# Deneigus_Controle_Deplacement.net
KiCad netlist of a schematic drawn in Altium Designer
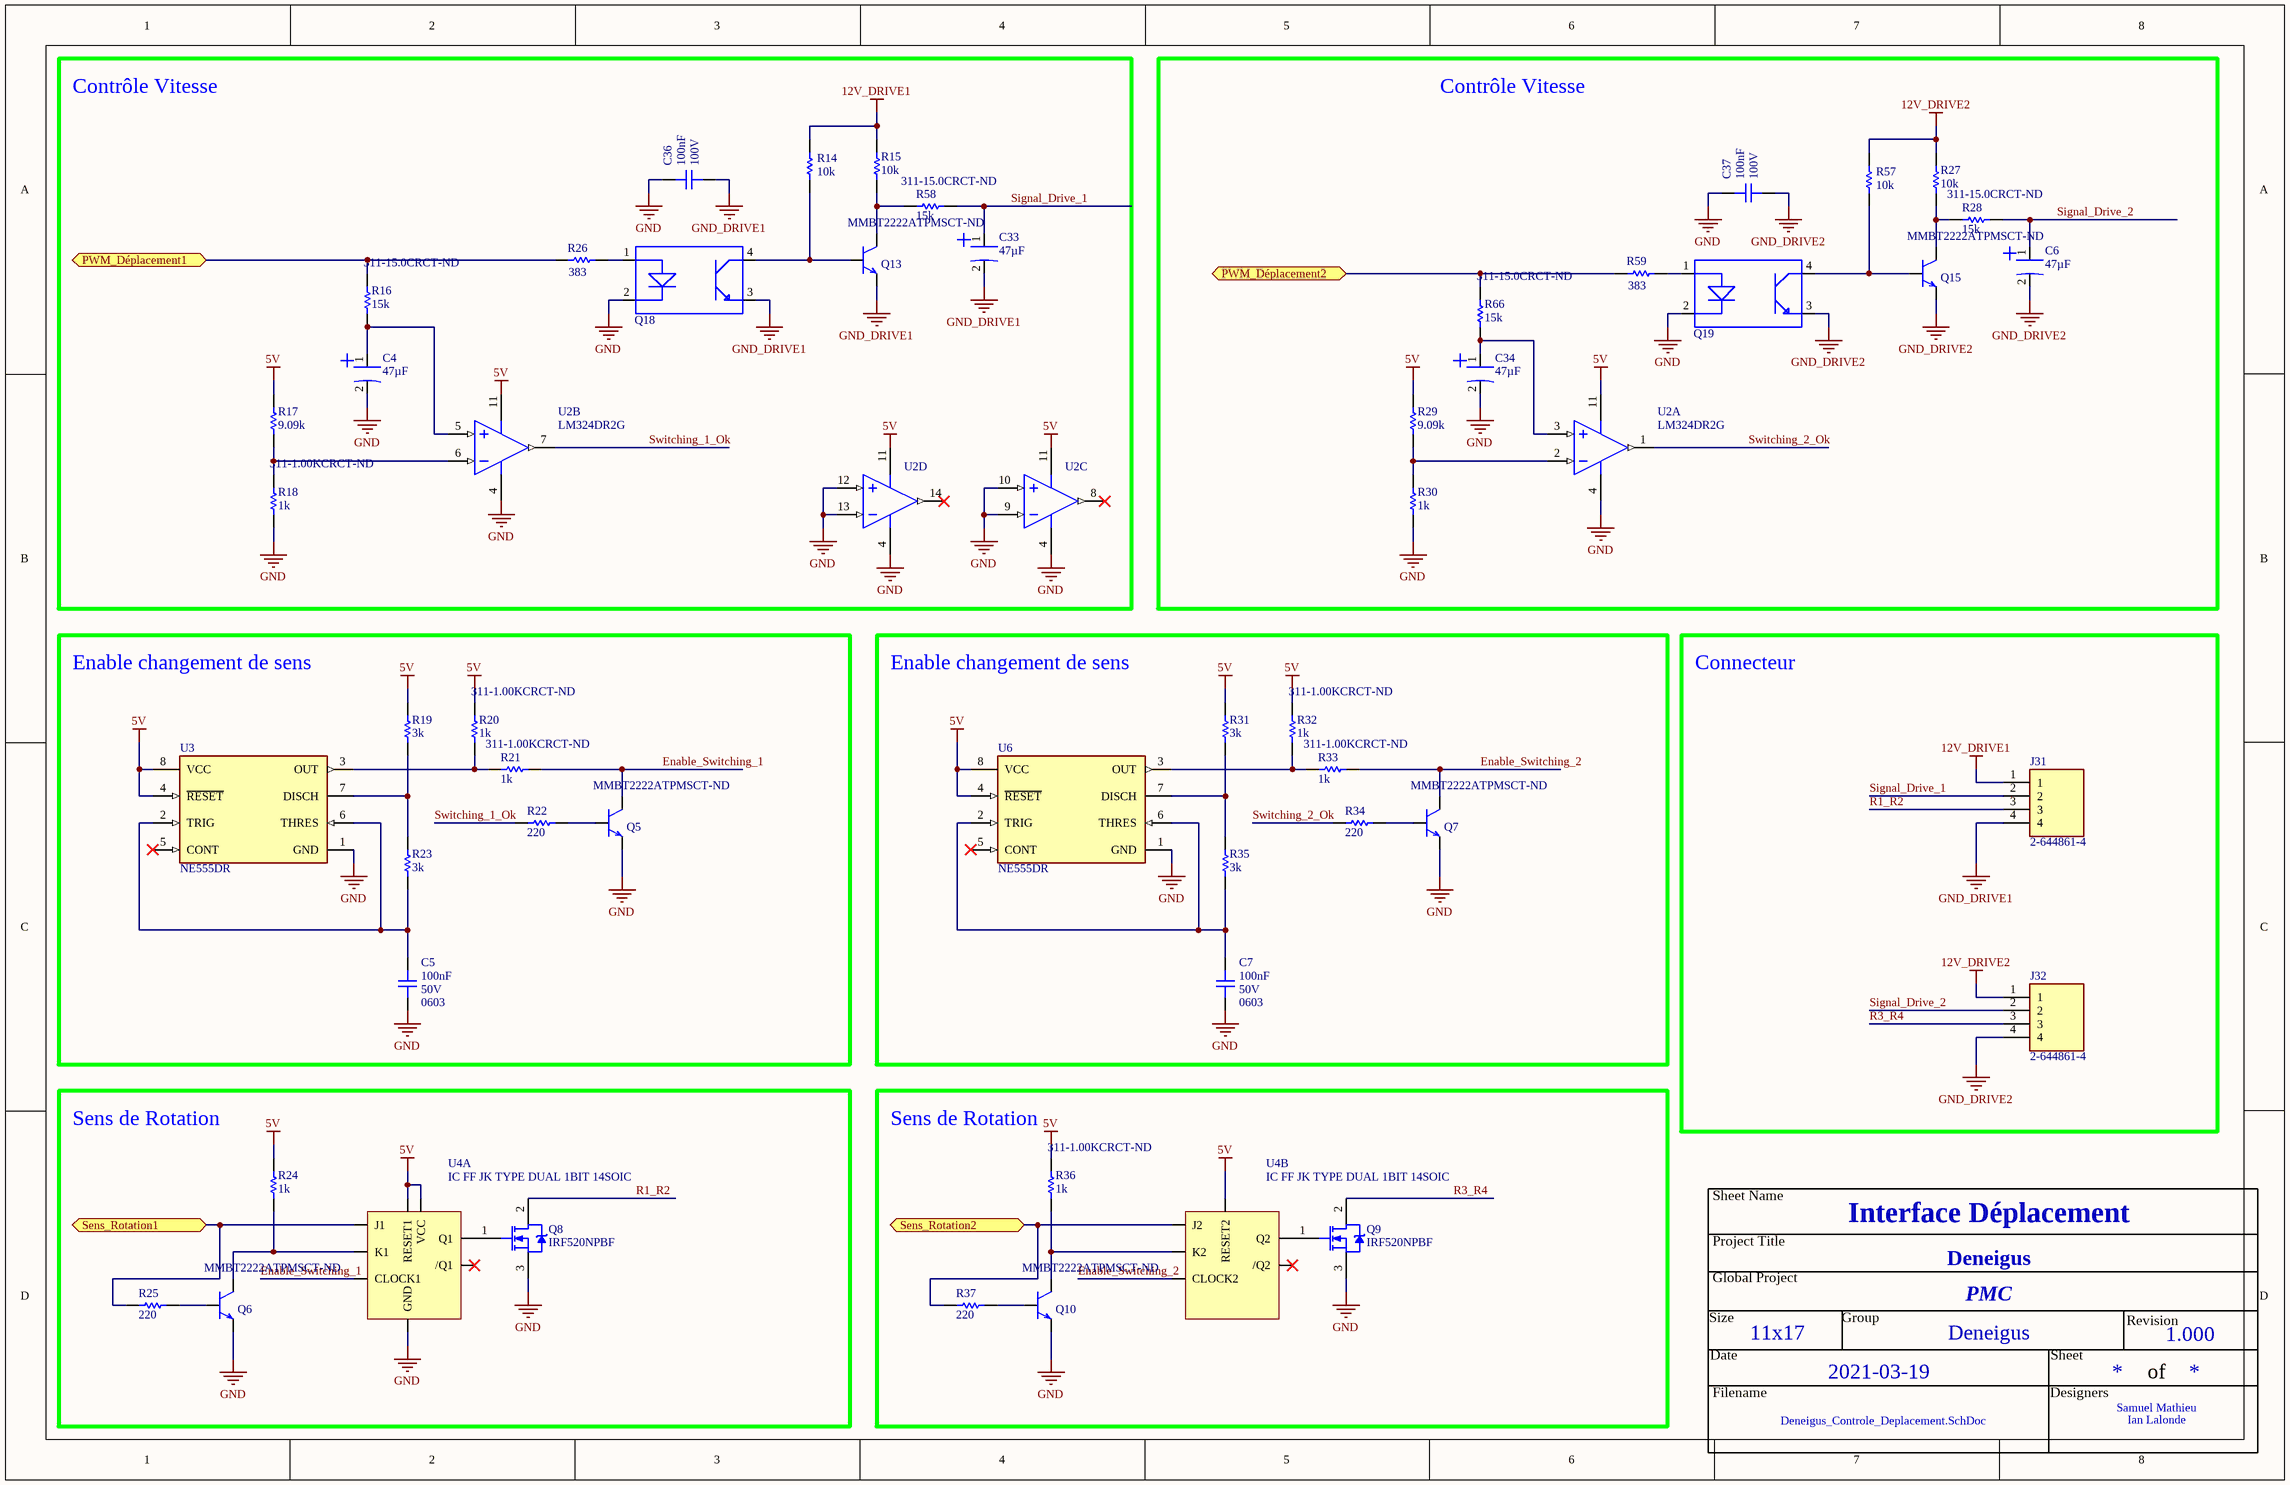
[diagram p0: Deneigus_Controle_Deplacement.SchDoc]

(export (version "E")
  (design (tool "Eeschema 10.0.6"))
  (components
    (comp (ref "C4")
      (value "47µF")
      (footprint "47uF")
      (fields
        (field (name "MFG") "Würth Elektronik")
        (field (name "MFG PART NUMBER") "875105344006")
        (field (name "Comment") "CAP ALUM POLY 47UF 20% 16V SMD")
      )
      (libsource (lib "S7CAS-APP1") (part "47µF SMD"))
    )
    (comp (ref "C5")
      (value "100nF")
      (footprint "CAP_0603")
      (description "CAP - 0603")
      (fields
        (field (name "VOLTAGE") "50V")
        (field (name "PACKAGE") "0603")
        (field (name "CREATEDBY") "Jonathan Bouchard")
      )
      (libsource (lib "S7CAS_LIB2021") (part "CAP - 0603"))
    )
    (comp (ref "C6")
      (value "47µF")
      (footprint "47uF")
      (fields
        (field (name "MFG") "Würth Elektronik")
        (field (name "MFG PART NUMBER") "875105344006")
        (field (name "Comment") "CAP ALUM POLY 47UF 20% 16V SMD")
      )
      (libsource (lib "S7CAS-APP1") (part "47µF SMD"))
    )
    (comp (ref "C7")
      (value "100nF")
      (footprint "CAP_0603")
      (description "CAP - 0603")
      (fields
        (field (name "VOLTAGE") "50V")
        (field (name "PACKAGE") "0603")
        (field (name "CREATEDBY") "Jonathan Bouchard")
      )
      (libsource (lib "S7CAS_LIB2021") (part "CAP - 0603"))
    )
    (comp (ref "C33")
      (value "47µF")
      (footprint "47uF")
      (fields
        (field (name "MFG") "Würth Elektronik")
        (field (name "MFG PART NUMBER") "875105344006")
        (field (name "Comment") "CAP ALUM POLY 47UF 20% 16V SMD")
      )
      (libsource (lib "S7CAS-APP1") (part "47µF SMD"))
    )
    (comp (ref "C34")
      (value "47µF")
      (footprint "47uF")
      (fields
        (field (name "MFG") "Würth Elektronik")
        (field (name "MFG PART NUMBER") "875105344006")
        (field (name "Comment") "CAP ALUM POLY 47UF 20% 16V SMD")
      )
      (libsource (lib "S7CAS-APP1") (part "47µF SMD"))
    )
    (comp (ref "C36")
      (value "100nF")
      (footprint "CAP_0805")
      (description "CAP - 0805")
      (fields
        (field (name "MFG") "Murata Electronics")
        (field (name "MFG PART NUMBER") "GRM21BR61H106ME43L")
        (field (name "VOLTAGE") "100V")
        (field (name "CREATEDBY") "Jonathan Bouchard")
      )
      (libsource (lib "S7CAS_LIB2021(1)") (part "CAP - 0805"))
    )
    (comp (ref "C37")
      (value "100nF")
      (footprint "CAP_0805")
      (description "CAP - 0805")
      (fields
        (field (name "MFG") "Murata Electronics")
        (field (name "MFG PART NUMBER") "GRM21BR61H106ME43L")
        (field (name "VOLTAGE") "100V")
        (field (name "CREATEDBY") "Jonathan Bouchard")
      )
      (libsource (lib "S7CAS_LIB2021(1)") (part "CAP - 0805"))
    )
    (comp (ref "J31")
      (value "2-644861-4")
      (footprint "TE_2-644861-4:TE_2-644861-4")
      (description "Connector Header Through Hole 4 position 0.100 (2.54mm)")
      (fields (field (name "MF") "TE Connectivity"))
      (libsource (lib "2-644861-4") (part "2-644861-4"))
    )
    (comp (ref "J32")
      (value "2-644861-4")
      (footprint "TE_2-644861-4:TE_2-644861-4")
      (description "Connector Header Through Hole 4 position 0.100 (2.54mm)")
      (fields (field (name "MF") "TE Connectivity"))
      (libsource (lib "2-644861-4") (part "2-644861-4"))
    )
    (comp (ref "Q5")
      (value "TRANS NPN 40V 0.2A SOT23")
      (footprint "SOT-23")
      (description "Transistor: 200mA 200mW NPN General-Purpose Amplifier, SOT-23, 7IN. Reel")
      (fields
        (field (name "MANUFACTURER") "MCC")
        (field (name "MANUFACTURER PART NUMBER") "MMBT3904-TP")
        (field (name "SUPPLIER PART NUMBER 1") "MMBT2222ATPMSCT-ND")
      )
      (libsource (lib "S7CAS-APP1") (part "NPN 3904 SMD"))
    )
    (comp (ref "Q6")
      (value "TRANS NPN 40V 0.2A SOT23")
      (footprint "SOT-23")
      (description "Transistor: 200mA 200mW NPN General-Purpose Amplifier, SOT-23, 7IN. Reel")
      (fields
        (field (name "MANUFACTURER") "MCC")
        (field (name "MANUFACTURER PART NUMBER") "MMBT3904-TP")
        (field (name "SUPPLIER PART NUMBER 1") "MMBT2222ATPMSCT-ND")
      )
      (libsource (lib "S7CAS-APP1") (part "NPN 3904 SMD"))
    )
    (comp (ref "Q7")
      (value "TRANS NPN 40V 0.2A SOT23")
      (footprint "SOT-23")
      (description "Transistor: 200mA 200mW NPN General-Purpose Amplifier, SOT-23, 7IN. Reel")
      (fields
        (field (name "MANUFACTURER") "MCC")
        (field (name "MANUFACTURER PART NUMBER") "MMBT3904-TP")
        (field (name "SUPPLIER PART NUMBER 1") "MMBT2222ATPMSCT-ND")
      )
      (libsource (lib "S7CAS-APP1") (part "NPN 3904 SMD"))
    )
    (comp (ref "Q8")
      (value "IRF520NPBF")
      (footprint "INTR-TO-220AB-3")
      (description "HEXFET(R) Power MOSFET, 100 V, 9.7 A, 0.2 Ohm, -55 to 175 degC, 3-Pin FM (TO-220AB), RoHS, Tube")
      (fields (field (name "POWER") "48W") (field (name "MANUFACTURER") "International Rectifier"))
      (libsource (lib "Université de Sherbrooke") (part "NEMOS-GDS-3_B"))
    )
    (comp (ref "Q9")
      (value "IRF520NPBF")
      (footprint "INTR-TO-220AB-3")
      (description "HEXFET(R) Power MOSFET, 100 V, 9.7 A, 0.2 Ohm, -55 to 175 degC, 3-Pin FM (TO-220AB), RoHS, Tube")
      (fields (field (name "POWER") "48W") (field (name "MANUFACTURER") "International Rectifier"))
      (libsource (lib "Université de Sherbrooke") (part "NEMOS-GDS-3_B"))
    )
    (comp (ref "Q10")
      (value "TRANS NPN 40V 0.2A SOT23")
      (footprint "SOT-23")
      (description "Transistor: 200mA 200mW NPN General-Purpose Amplifier, SOT-23, 7IN. Reel")
      (fields
        (field (name "MANUFACTURER") "MCC")
        (field (name "MANUFACTURER PART NUMBER") "MMBT3904-TP")
        (field (name "SUPPLIER PART NUMBER 1") "MMBT2222ATPMSCT-ND")
      )
      (libsource (lib "S7CAS-APP1") (part "NPN 3904 SMD"))
    )
    (comp (ref "Q13")
      (value "TRANS NPN 40V 0.2A SOT23")
      (footprint "SOT-23")
      (description "Transistor: 200mA 200mW NPN General-Purpose Amplifier, SOT-23, 7IN. Reel")
      (fields
        (field (name "MANUFACTURER") "MCC")
        (field (name "MANUFACTURER PART NUMBER") "MMBT3904-TP")
        (field (name "SUPPLIER PART NUMBER 1") "MMBT2222ATPMSCT-ND")
      )
      (libsource (lib "S7CAS-APP1") (part "NPN 3904 SMD"))
    )
    (comp (ref "Q15")
      (value "TRANS NPN 40V 0.2A SOT23")
      (footprint "SOT-23")
      (description "Transistor: 200mA 200mW NPN General-Purpose Amplifier, SOT-23, 7IN. Reel")
      (fields
        (field (name "MANUFACTURER") "MCC")
        (field (name "MANUFACTURER PART NUMBER") "MMBT3904-TP")
        (field (name "SUPPLIER PART NUMBER 1") "MMBT2222ATPMSCT-ND")
      )
      (libsource (lib "S7CAS-APP1") (part "NPN 3904 SMD"))
    )
    (comp (ref "Q18")
      (value "WL-OCPT OPTOCOUPLER PHOTOTRANSIS")
      (footprint "WL-OCPT OPTOCOUPLER PHOTOTRANSIS")
      (description "Optoisolator Transistor Output 3750Vrms 1 Channel 4-SOP")
      (libsource (lib "S7CAS-APP1") (part "WL-OCPT OPTOCOUPLER PHOTOTRANSIS"))
    )
    (comp (ref "Q19")
      (value "WL-OCPT OPTOCOUPLER PHOTOTRANSIS")
      (footprint "WL-OCPT OPTOCOUPLER PHOTOTRANSIS")
      (description "Optoisolator Transistor Output 3750Vrms 1 Channel 4-SOP")
      (libsource (lib "S7CAS-APP1") (part "WL-OCPT OPTOCOUPLER PHOTOTRANSIS"))
    )
    (comp (ref "R14")
      (value "10k")
      (footprint "RES_0805")
      (description "Resistor")
      (fields (field (name "Comment") "Res1") (field (name "PUBLISHER") "Altium Limited"))
      (libsource (lib "Miscellaneous Devices") (part "Res1"))
    )
    (comp (ref "R15")
      (value "10k")
      (footprint "RES_0805")
      (description "Resistor")
      (fields (field (name "Comment") "Res1") (field (name "PUBLISHER") "Altium Limited"))
      (libsource (lib "Miscellaneous Devices") (part "Res1"))
    )
    (comp (ref "R16")
      (value "15k")
      (footprint "RES_0805")
      (description "Resistor")
      (fields
        (field (name "SUPPLIER PART NUMBER 1") "311-15.0CRCT-ND")
        (field (name "Comment") "Res1")
        (field (name "PUBLISHER") "Altium Limited")
      )
      (libsource (lib "Miscellaneous Devices") (part "Res1"))
    )
    (comp (ref "R17")
      (value "9.09k")
      (footprint "RES_0805")
      (description "Resistor")
      (fields (field (name "Comment") "Res1") (field (name "PUBLISHER") "Altium Limited"))
      (libsource (lib "Miscellaneous Devices") (part "Res1"))
    )
    (comp (ref "R18")
      (value "1k")
      (footprint "RES_0805")
      (description "Resistor")
      (fields
        (field (name "SUPPLIER PART NUMBER 1") "311-1.00KCRCT-ND")
        (field (name "Comment") "Res1")
        (field (name "PUBLISHER") "Altium Limited")
      )
      (libsource (lib "Miscellaneous Devices") (part "Res1"))
    )
    (comp (ref "R19")
      (value "3k")
      (footprint "RES_0805")
      (description "Resistor")
      (fields (field (name "Comment") "Res1") (field (name "PUBLISHER") "Altium Limited"))
      (libsource (lib "Miscellaneous Devices") (part "Res1"))
    )
    (comp (ref "R20")
      (value "1k")
      (footprint "RES_0805")
      (description "Resistor")
      (fields
        (field (name "SUPPLIER PART NUMBER 1") "311-1.00KCRCT-ND")
        (field (name "Comment") "Res1")
        (field (name "PUBLISHER") "Altium Limited")
      )
      (libsource (lib "Miscellaneous Devices") (part "Res1"))
    )
    (comp (ref "R21")
      (value "1k")
      (footprint "RES_0805")
      (description "Resistor")
      (fields
        (field (name "SUPPLIER PART NUMBER 1") "311-1.00KCRCT-ND")
        (field (name "Comment") "Res1")
        (field (name "PUBLISHER") "Altium Limited")
      )
      (libsource (lib "Miscellaneous Devices") (part "Res1"))
    )
    (comp (ref "R22")
      (value "220")
      (footprint "RES_0805")
      (description "Resistor")
      (fields (field (name "Comment") "Res1") (field (name "PUBLISHER") "Altium Limited"))
      (libsource (lib "Miscellaneous Devices") (part "Res1"))
    )
    (comp (ref "R23")
      (value "3k")
      (footprint "RES_0805")
      (description "Resistor")
      (fields (field (name "Comment") "Res1") (field (name "PUBLISHER") "Altium Limited"))
      (libsource (lib "Miscellaneous Devices") (part "Res1"))
    )
    (comp (ref "R24")
      (value "1k")
      (footprint "RES_0805")
      (description "Resistor")
      (fields (field (name "Comment") "Res1") (field (name "PUBLISHER") "Altium Limited"))
      (libsource (lib "Miscellaneous Devices") (part "Res1"))
    )
    (comp (ref "R25")
      (value "220")
      (footprint "RES_0805")
      (description "Resistor")
      (fields (field (name "Comment") "Res1") (field (name "PUBLISHER") "Altium Limited"))
      (libsource (lib "Miscellaneous Devices") (part "Res1"))
    )
    (comp (ref "R26")
      (value "383")
      (footprint "RES_0805")
      (description "Resistor")
      (fields (field (name "Comment") "Res1") (field (name "PUBLISHER") "Altium Limited"))
      (libsource (lib "Miscellaneous Devices") (part "Res1"))
    )
    (comp (ref "R27")
      (value "10k")
      (footprint "RES_0805")
      (description "Resistor")
      (fields (field (name "Comment") "Res1") (field (name "PUBLISHER") "Altium Limited"))
      (libsource (lib "Miscellaneous Devices") (part "Res1"))
    )
    (comp (ref "R28")
      (value "15k")
      (footprint "RES_0805")
      (description "Resistor")
      (fields
        (field (name "SUPPLIER PART NUMBER 1") "311-15.0CRCT-ND")
        (field (name "Comment") "Res1")
        (field (name "PUBLISHER") "Altium Limited")
      )
      (libsource (lib "Miscellaneous Devices") (part "Res1"))
    )
    (comp (ref "R29")
      (value "9.09k")
      (footprint "RES_0805")
      (description "Resistor")
      (fields (field (name "Comment") "Res1") (field (name "PUBLISHER") "Altium Limited"))
      (libsource (lib "Miscellaneous Devices") (part "Res1"))
    )
    (comp (ref "R30")
      (value "1k")
      (footprint "RES_0805")
      (description "Resistor")
      (fields (field (name "Comment") "Res1") (field (name "PUBLISHER") "Altium Limited"))
      (libsource (lib "Miscellaneous Devices") (part "Res1"))
    )
    (comp (ref "R31")
      (value "3k")
      (footprint "RES_0805")
      (description "Resistor")
      (fields (field (name "Comment") "Res1") (field (name "PUBLISHER") "Altium Limited"))
      (libsource (lib "Miscellaneous Devices") (part "Res1"))
    )
    (comp (ref "R32")
      (value "1k")
      (footprint "RES_0805")
      (description "Resistor")
      (fields
        (field (name "SUPPLIER PART NUMBER 1") "311-1.00KCRCT-ND")
        (field (name "Comment") "Res1")
        (field (name "PUBLISHER") "Altium Limited")
      )
      (libsource (lib "Miscellaneous Devices") (part "Res1"))
    )
    (comp (ref "R33")
      (value "1k")
      (footprint "RES_0805")
      (description "Resistor")
      (fields
        (field (name "SUPPLIER PART NUMBER 1") "311-1.00KCRCT-ND")
        (field (name "Comment") "Res1")
        (field (name "PUBLISHER") "Altium Limited")
      )
      (libsource (lib "Miscellaneous Devices") (part "Res1"))
    )
    (comp (ref "R34")
      (value "220")
      (footprint "RES_0805")
      (description "Resistor")
      (fields (field (name "Comment") "Res1") (field (name "PUBLISHER") "Altium Limited"))
      (libsource (lib "Miscellaneous Devices") (part "Res1"))
    )
    (comp (ref "R35")
      (value "3k")
      (footprint "RES_0805")
      (description "Resistor")
      (fields (field (name "Comment") "Res1") (field (name "PUBLISHER") "Altium Limited"))
      (libsource (lib "Miscellaneous Devices") (part "Res1"))
    )
    (comp (ref "R36")
      (value "1k")
      (footprint "RES_0805")
      (description "Resistor")
      (fields
        (field (name "SUPPLIER PART NUMBER 1") "311-1.00KCRCT-ND")
        (field (name "Comment") "Res1")
        (field (name "PUBLISHER") "Altium Limited")
      )
      (libsource (lib "Miscellaneous Devices") (part "Res1"))
    )
    (comp (ref "R37")
      (value "220")
      (footprint "RES_0805")
      (description "Resistor")
      (fields (field (name "Comment") "Res1") (field (name "PUBLISHER") "Altium Limited"))
      (libsource (lib "Miscellaneous Devices") (part "Res1"))
    )
    (comp (ref "R57")
      (value "10k")
      (footprint "RES_0805")
      (description "Resistor")
      (fields (field (name "Comment") "Res1") (field (name "PUBLISHER") "Altium Limited"))
      (libsource (lib "Miscellaneous Devices") (part "Res1"))
    )
    (comp (ref "R58")
      (value "15k")
      (footprint "RES_0805")
      (description "Resistor")
      (fields
        (field (name "SUPPLIER PART NUMBER 1") "311-15.0CRCT-ND")
        (field (name "Comment") "Res1")
        (field (name "PUBLISHER") "Altium Limited")
      )
      (libsource (lib "Miscellaneous Devices") (part "Res1"))
    )
    (comp (ref "R59")
      (value "383")
      (footprint "RES_0805")
      (description "Resistor")
      (fields (field (name "Comment") "Res1") (field (name "PUBLISHER") "Altium Limited"))
      (libsource (lib "Miscellaneous Devices") (part "Res1"))
    )
    (comp (ref "R66")
      (value "15k")
      (footprint "RES_0805")
      (description "Resistor")
      (fields
        (field (name "SUPPLIER PART NUMBER 1") "311-15.0CRCT-ND")
        (field (name "Comment") "Res1")
        (field (name "PUBLISHER") "Altium Limited")
      )
      (libsource (lib "Miscellaneous Devices") (part "Res1"))
    )
    (comp (ref "U2")
      (value "LM324DR2G")
      (footprint "ONSC-SOIC-14-751A-03_V")
      (fields (field (name "MANUFACTURER") "On Semiconductor"))
      (libsource (lib "Altium Content Vault") (part "ONSC-LM224_324_2902_NCV2902-14"))
    )
    (comp (ref "U3")
      (value "NE555DR")
      (footprint "FP-D0008A-IPC_A")
      (description "IC OSC SGL TIMER 100KHZ 8-SOIC")
      (libsource (lib "Altium Content Vault") (part "a29bba90211dec1890110b94dad7d53"))
    )
    (comp (ref "U4")
      (value "IC FF JK TYPE DUAL 1BIT 14SOIC")
      (footprint "SOIC127P600X175-14N")
      (description "Flip Flop Element JK Type Bit Negative Edge 14-SOIC (0.154\", 3.90mm Width)")
      (libsource (lib "S7CAS-APP1") (part "Dual JK flip-flop"))
    )
    (comp (ref "U6")
      (value "NE555DR")
      (footprint "FP-D0008A-IPC_A")
      (description "IC OSC SGL TIMER 100KHZ 8-SOIC")
      (libsource (lib "Altium Content Vault") (part "a29bba90211dec1890110b94dad7d53"))
    )
  )
  (nets
    (net (code "1") (name "/Enable_Switching_1") (class "Default")
      (node (ref "Q5") (pin "3") (pinfunction "3_3") (pintype "passive"))
      (node (ref "R21") (pin "2") (pinfunction "2_2") (pintype "passive"))
      (node (ref "U4") (pin "1") (pinfunction "CLOCK1_1") (pintype "passive"))
    )
    (net (code "2") (name "/Enable_Switching_2") (class "Default")
      (node (ref "Q7") (pin "3") (pinfunction "3_3") (pintype "passive"))
      (node (ref "R33") (pin "2") (pinfunction "2_2") (pintype "passive"))
      (node (ref "U4") (pin "5") (pinfunction "CLOCK2_5") (pintype "passive"))
    )
    (net (code "3") (name "/PWM_Déplacement1") (class "Default")
      (node (ref "R16") (pin "1") (pinfunction "1_1") (pintype "passive"))
      (node (ref "R26") (pin "1") (pinfunction "1_1") (pintype "passive"))
    )
    (net (code "4") (name "/PWM_Déplacement2") (class "Default")
      (node (ref "R59") (pin "1") (pinfunction "1_1") (pintype "passive"))
      (node (ref "R66") (pin "1") (pinfunction "1_1") (pintype "passive"))
    )
    (net (code "5") (name "/R1_R2") (class "Default")
      (node (ref "J31") (pin "3") (pinfunction "3_3") (pintype "passive"))
      (node (ref "Q8") (pin "2") (pinfunction "D_2") (pintype "passive"))
    )
    (net (code "6") (name "/R3_R4") (class "Default")
      (node (ref "J32") (pin "3") (pinfunction "3_3") (pintype "passive"))
      (node (ref "Q9") (pin "2") (pinfunction "D_2") (pintype "passive"))
    )
    (net (code "7") (name "/Sens_Rotation1") (class "Default")
      (node (ref "R25") (pin "1") (pinfunction "1_1") (pintype "passive"))
      (node (ref "U4") (pin "14") (pinfunction "J1_14") (pintype "passive"))
    )
    (net (code "8") (name "/Sens_Rotation2") (class "Default")
      (node (ref "R37") (pin "1") (pinfunction "1_1") (pintype "passive"))
      (node (ref "U4") (pin "7") (pinfunction "J2_7") (pintype "passive"))
    )
    (net (code "9") (name "/Signal_Drive_1") (class "Default")
      (node (ref "C33") (pin "1") (pinfunction "1_1") (pintype "passive"))
      (node (ref "J31") (pin "2") (pinfunction "2_2") (pintype "passive"))
      (node (ref "R58") (pin "2") (pinfunction "2_2") (pintype "passive"))
    )
    (net (code "10") (name "/Signal_Drive_2") (class "Default")
      (node (ref "C6") (pin "1") (pinfunction "1_1") (pintype "passive"))
      (node (ref "J32") (pin "2") (pinfunction "2_2") (pintype "passive"))
      (node (ref "R28") (pin "2") (pinfunction "2_2") (pintype "passive"))
    )
    (net (code "11") (name "/Switching_1_Ok") (class "Default")
      (node (ref "R22") (pin "1") (pinfunction "1_1") (pintype "passive"))
      (node (ref "U2") (pin "7") (pinfunction "OUT2_7") (pintype "output"))
    )
    (net (code "12") (name "/Switching_2_Ok") (class "Default")
      (node (ref "R34") (pin "1") (pinfunction "1_1") (pintype "passive"))
      (node (ref "U2") (pin "1") (pinfunction "OUT1_1") (pintype "output"))
    )
    (net (code "13") (name "5V") (class "Default")
      (node (ref "R17") (pin "2") (pinfunction "2_2") (pintype "passive"))
      (node (ref "R19") (pin "2") (pinfunction "2_2") (pintype "passive"))
      (node (ref "R20") (pin "2") (pinfunction "2_2") (pintype "passive"))
      (node (ref "R24") (pin "2") (pinfunction "2_2") (pintype "passive"))
      (node (ref "R29") (pin "2") (pinfunction "2_2") (pintype "passive"))
      (node (ref "R31") (pin "2") (pinfunction "2_2") (pintype "passive"))
      (node (ref "R32") (pin "2") (pinfunction "2_2") (pintype "passive"))
      (node (ref "R36") (pin "2") (pinfunction "2_2") (pintype "passive"))
      (node (ref "U2") (pin "11") (pinfunction "VEE/GND_11") (pintype "power_in"))
      (node (ref "U3") (pin "4") (pinfunction "~{RESET}_4") (pintype "input"))
      (node (ref "U3") (pin "8") (pinfunction "VCC_8") (pintype "power_in"))
      (node (ref "U4") (pin "2") (pinfunction "RESET1_2") (pintype "passive"))
      (node (ref "U4") (pin "4") (pinfunction "VCC_4") (pintype "passive"))
      (node (ref "U4") (pin "6") (pinfunction "RESET2_6") (pintype "passive"))
      (node (ref "U6") (pin "4") (pinfunction "~{RESET}_4") (pintype "input"))
      (node (ref "U6") (pin "8") (pinfunction "VCC_8") (pintype "power_in"))
    )
    (net (code "14") (name "12V_DRIVE1") (class "Default")
      (node (ref "J31") (pin "1") (pinfunction "1_1") (pintype "passive"))
      (node (ref "R14") (pin "1") (pinfunction "1_1") (pintype "passive"))
      (node (ref "R15") (pin "2") (pinfunction "2_2") (pintype "passive"))
    )
    (net (code "15") (name "12V_DRIVE2") (class "Default")
      (node (ref "J32") (pin "1") (pinfunction "1_1") (pintype "passive"))
      (node (ref "R27") (pin "2") (pinfunction "2_2") (pintype "passive"))
      (node (ref "R57") (pin "1") (pinfunction "1_1") (pintype "passive"))
    )
    (net (code "16") (name "GND") (class "Default")
      (node (ref "C34") (pin "2") (pinfunction "2_2") (pintype "passive"))
      (node (ref "C36") (pin "2") (pinfunction "2_2") (pintype "passive"))
      (node (ref "C37") (pin "2") (pinfunction "2_2") (pintype "passive"))
      (node (ref "C4") (pin "2") (pinfunction "2_2") (pintype "passive"))
      (node (ref "C5") (pin "1") (pinfunction "1_1") (pintype "passive"))
      (node (ref "C7") (pin "1") (pinfunction "1_1") (pintype "passive"))
      (node (ref "Q10") (pin "2") (pinfunction "2_2") (pintype "passive"))
      (node (ref "Q18") (pin "2") (pinfunction "2_2") (pintype "passive"))
      (node (ref "Q19") (pin "2") (pinfunction "2_2") (pintype "passive"))
      (node (ref "Q5") (pin "2") (pinfunction "2_2") (pintype "passive"))
      (node (ref "Q6") (pin "2") (pinfunction "2_2") (pintype "passive"))
      (node (ref "Q7") (pin "2") (pinfunction "2_2") (pintype "passive"))
      (node (ref "Q8") (pin "3") (pinfunction "S_3") (pintype "passive"))
      (node (ref "Q9") (pin "3") (pinfunction "S_3") (pintype "passive"))
      (node (ref "R18") (pin "1") (pinfunction "1_1") (pintype "passive"))
      (node (ref "R30") (pin "1") (pinfunction "1_1") (pintype "passive"))
      (node (ref "U2") (pin "10") (pinfunction "IN3+_10") (pintype "input"))
      (node (ref "U2") (pin "12") (pinfunction "IN4+_12") (pintype "input"))
      (node (ref "U2") (pin "13") (pinfunction "IN4-_13") (pintype "input"))
      (node (ref "U2") (pin "4") (pinfunction "VCC_4") (pintype "power_in"))
      (node (ref "U2") (pin "9") (pinfunction "IN3-_9") (pintype "input"))
      (node (ref "U3") (pin "1") (pinfunction "GND_1") (pintype "power_in"))
      (node (ref "U4") (pin "11") (pinfunction "GND_11") (pintype "passive"))
      (node (ref "U6") (pin "1") (pinfunction "GND_1") (pintype "power_in"))
    )
    (net (code "17") (name "GND_DRIVE1") (class "Default")
      (node (ref "C33") (pin "2") (pinfunction "2_2") (pintype "passive"))
      (node (ref "C36") (pin "1") (pinfunction "1_1") (pintype "passive"))
      (node (ref "J31") (pin "4") (pinfunction "4_4") (pintype "passive"))
      (node (ref "Q13") (pin "2") (pinfunction "2_2") (pintype "passive"))
      (node (ref "Q18") (pin "3") (pinfunction "3_3") (pintype "passive"))
    )
    (net (code "18") (name "GND_DRIVE2") (class "Default")
      (node (ref "C37") (pin "1") (pinfunction "1_1") (pintype "passive"))
      (node (ref "C6") (pin "2") (pinfunction "2_2") (pintype "passive"))
      (node (ref "J32") (pin "4") (pinfunction "4_4") (pintype "passive"))
      (node (ref "Q15") (pin "2") (pinfunction "2_2") (pintype "passive"))
      (node (ref "Q19") (pin "3") (pinfunction "3_3") (pintype "passive"))
    )
    (net (code "19") (name "Net-(Q5-Pad1)") (class "Default")
      (node (ref "Q5") (pin "1") (pinfunction "1_1") (pintype "passive"))
      (node (ref "R22") (pin "2") (pinfunction "2_2") (pintype "passive"))
    )
    (net (code "20") (name "Net-(Q6-Pad1)") (class "Default")
      (node (ref "Q6") (pin "1") (pinfunction "1_1") (pintype "passive"))
      (node (ref "R25") (pin "2") (pinfunction "2_2") (pintype "passive"))
    )
    (net (code "21") (name "Net-(Q7-Pad1)") (class "Default")
      (node (ref "Q7") (pin "1") (pinfunction "1_1") (pintype "passive"))
      (node (ref "R34") (pin "2") (pinfunction "2_2") (pintype "passive"))
    )
    (net (code "22") (name "Net-(Q8-G)") (class "Default")
      (node (ref "Q8") (pin "1") (pinfunction "G_1") (pintype "passive"))
      (node (ref "U4") (pin "12") (pinfunction "Q1_12") (pintype "passive"))
    )
    (net (code "23") (name "Net-(Q9-G)") (class "Default")
      (node (ref "Q9") (pin "1") (pinfunction "G_1") (pintype "passive"))
      (node (ref "U4") (pin "9") (pinfunction "Q2_9") (pintype "passive"))
    )
    (net (code "24") (name "Net-(Q10-Pad1)") (class "Default")
      (node (ref "Q10") (pin "1") (pinfunction "1_1") (pintype "passive"))
      (node (ref "R37") (pin "2") (pinfunction "2_2") (pintype "passive"))
    )
    (net (code "25") (name "Net-(Q13-Pad1)") (class "Default")
      (node (ref "Q13") (pin "1") (pinfunction "1_1") (pintype "passive"))
      (node (ref "Q18") (pin "4") (pinfunction "4_4") (pintype "passive"))
      (node (ref "R14") (pin "2") (pinfunction "2_2") (pintype "passive"))
    )
    (net (code "26") (name "Net-(Q13-Pad3)") (class "Default")
      (node (ref "Q13") (pin "3") (pinfunction "3_3") (pintype "passive"))
      (node (ref "R15") (pin "1") (pinfunction "1_1") (pintype "passive"))
      (node (ref "R58") (pin "1") (pinfunction "1_1") (pintype "passive"))
    )
    (net (code "27") (name "Net-(Q15-Pad1)") (class "Default")
      (node (ref "Q15") (pin "1") (pinfunction "1_1") (pintype "passive"))
      (node (ref "Q19") (pin "4") (pinfunction "4_4") (pintype "passive"))
      (node (ref "R57") (pin "2") (pinfunction "2_2") (pintype "passive"))
    )
    (net (code "28") (name "Net-(Q15-Pad3)") (class "Default")
      (node (ref "Q15") (pin "3") (pinfunction "3_3") (pintype "passive"))
      (node (ref "R27") (pin "1") (pinfunction "1_1") (pintype "passive"))
      (node (ref "R28") (pin "1") (pinfunction "1_1") (pintype "passive"))
    )
    (net (code "29") (name "Net-(Q18-Pad1)") (class "Default")
      (node (ref "Q18") (pin "1") (pinfunction "1_1") (pintype "passive"))
      (node (ref "R26") (pin "2") (pinfunction "2_2") (pintype "passive"))
    )
    (net (code "30") (name "Net-(Q19-Pad1)") (class "Default")
      (node (ref "Q19") (pin "1") (pinfunction "1_1") (pintype "passive"))
      (node (ref "R59") (pin "2") (pinfunction "2_2") (pintype "passive"))
    )
    (net (code "31") (name "Net-(U2A-IN1+)") (class "Default")
      (node (ref "C34") (pin "1") (pinfunction "1_1") (pintype "passive"))
      (node (ref "R66") (pin "2") (pinfunction "2_2") (pintype "passive"))
      (node (ref "U2") (pin "3") (pinfunction "IN1+_3") (pintype "input"))
    )
    (net (code "32") (name "Net-(U2A-IN1-)") (class "Default")
      (node (ref "R29") (pin "1") (pinfunction "1_1") (pintype "passive"))
      (node (ref "R30") (pin "2") (pinfunction "2_2") (pintype "passive"))
      (node (ref "U2") (pin "2") (pinfunction "IN1-_2") (pintype "input"))
    )
    (net (code "33") (name "Net-(U2B-IN2+)") (class "Default")
      (node (ref "C4") (pin "1") (pinfunction "1_1") (pintype "passive"))
      (node (ref "R16") (pin "2") (pinfunction "2_2") (pintype "passive"))
      (node (ref "U2") (pin "5") (pinfunction "IN2+_5") (pintype "input"))
    )
    (net (code "34") (name "Net-(U2B-IN2-)") (class "Default")
      (node (ref "R17") (pin "1") (pinfunction "1_1") (pintype "passive"))
      (node (ref "R18") (pin "2") (pinfunction "2_2") (pintype "passive"))
      (node (ref "U2") (pin "6") (pinfunction "IN2-_6") (pintype "input"))
    )
    (net (code "35") (name "Net-(U3-DISCH)") (class "Default")
      (node (ref "R19") (pin "1") (pinfunction "1_1") (pintype "passive"))
      (node (ref "R23") (pin "2") (pinfunction "2_2") (pintype "passive"))
      (node (ref "U3") (pin "7") (pinfunction "DISCH_7") (pintype "open_collector"))
    )
    (net (code "36") (name "Net-(U3-OUT)") (class "Default")
      (node (ref "R20") (pin "1") (pinfunction "1_1") (pintype "passive"))
      (node (ref "R21") (pin "1") (pinfunction "1_1") (pintype "passive"))
      (node (ref "U3") (pin "3") (pinfunction "OUT_3") (pintype "output"))
    )
    (net (code "37") (name "Net-(U3-THRES)") (class "Default")
      (node (ref "C5") (pin "2") (pinfunction "2_2") (pintype "passive"))
      (node (ref "R23") (pin "1") (pinfunction "1_1") (pintype "passive"))
      (node (ref "U3") (pin "2") (pinfunction "TRIG_2") (pintype "input"))
      (node (ref "U3") (pin "6") (pinfunction "THRES_6") (pintype "input"))
    )
    (net (code "38") (name "Net-(U4A-K1)") (class "Default")
      (node (ref "Q6") (pin "3") (pinfunction "3_3") (pintype "passive"))
      (node (ref "R24") (pin "1") (pinfunction "1_1") (pintype "passive"))
      (node (ref "U4") (pin "3") (pinfunction "K1_3") (pintype "passive"))
    )
    (net (code "39") (name "Net-(U4B-K2)") (class "Default")
      (node (ref "Q10") (pin "3") (pinfunction "3_3") (pintype "passive"))
      (node (ref "R36") (pin "1") (pinfunction "1_1") (pintype "passive"))
      (node (ref "U4") (pin "10") (pinfunction "K2_10") (pintype "passive"))
    )
    (net (code "40") (name "Net-(U6-DISCH)") (class "Default")
      (node (ref "R31") (pin "1") (pinfunction "1_1") (pintype "passive"))
      (node (ref "R35") (pin "2") (pinfunction "2_2") (pintype "passive"))
      (node (ref "U6") (pin "7") (pinfunction "DISCH_7") (pintype "open_collector"))
    )
    (net (code "41") (name "Net-(U6-OUT)") (class "Default")
      (node (ref "R32") (pin "1") (pinfunction "1_1") (pintype "passive"))
      (node (ref "R33") (pin "1") (pinfunction "1_1") (pintype "passive"))
      (node (ref "U6") (pin "3") (pinfunction "OUT_3") (pintype "output"))
    )
    (net (code "42") (name "Net-(U6-THRES)") (class "Default")
      (node (ref "C7") (pin "2") (pinfunction "2_2") (pintype "passive"))
      (node (ref "R35") (pin "1") (pinfunction "1_1") (pintype "passive"))
      (node (ref "U6") (pin "2") (pinfunction "TRIG_2") (pintype "input"))
      (node (ref "U6") (pin "6") (pinfunction "THRES_6") (pintype "input"))
    )
    (net (code "43") (name "unconnected-(U2C-OUT3-Pad8)") (class "Default")
      (node (ref "U2") (pin "8") (pinfunction "OUT3_8") (pintype "output+no_connect"))
    )
    (net (code "44") (name "unconnected-(U2D-OUT4-Pad14)") (class "Default")
      (node (ref "U2") (pin "14") (pinfunction "OUT4_14") (pintype "output+no_connect"))
    )
    (net (code "45") (name "unconnected-(U3-CONT-Pad5)") (class "Default")
      (node (ref "U3") (pin "5") (pinfunction "CONT_5") (pintype "input+no_connect"))
    )
    (net (code "46") (name "unconnected-(U4A-{slash}Q1-Pad13)") (class "Default")
      (node (ref "U4") (pin "13") (pinfunction "/Q1_13") (pintype "passive+no_connect"))
    )
    (net (code "47") (name "unconnected-(U4B-{slash}Q2-Pad8)") (class "Default")
      (node (ref "U4") (pin "8") (pinfunction "/Q2_8") (pintype "passive+no_connect"))
    )
    (net (code "48") (name "unconnected-(U6-CONT-Pad5)") (class "Default")
      (node (ref "U6") (pin "5") (pinfunction "CONT_5") (pintype "input+no_connect"))
    )
  )
)
